# rbbb.net
KiCad netlist of a schematic drawn in EAGLE
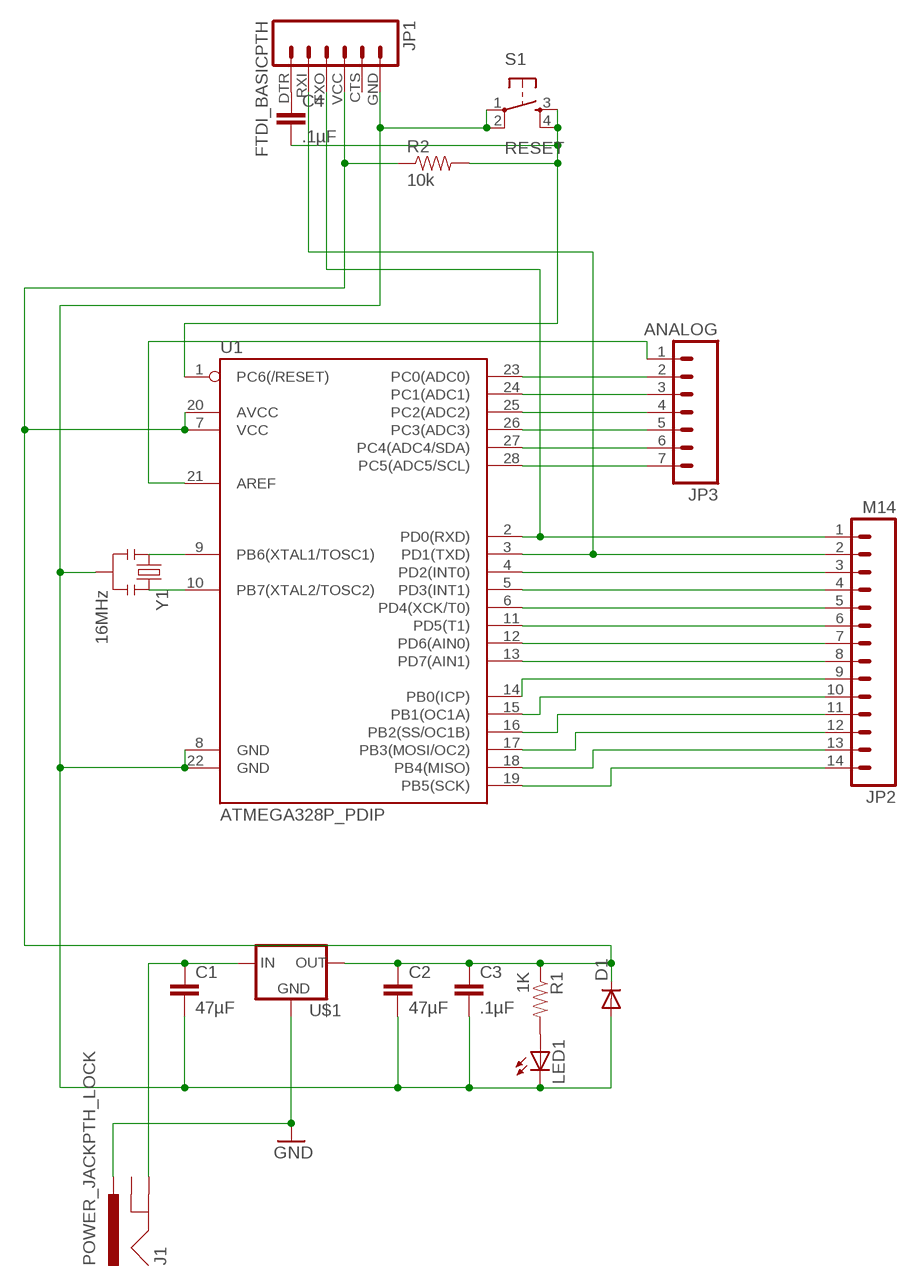
[diagram p0: schematic, sheet 1]

(export (version "E")
  (design (tool "Eeschema 10.0.6"))
  (components
    (comp (ref "C1")
      (value "47µF")
      (footprint "eagle-import:CAP-PTH-SMALL")
      (libsource (lib "eagle-import") (part "CAPPTH"))
    )
    (comp (ref "C2")
      (value "47µF")
      (footprint "eagle-import:CAP-PTH-SMALL")
      (libsource (lib "eagle-import") (part "CAPPTH"))
    )
    (comp (ref "C3")
      (value ".1µF")
      (footprint "eagle-import:CAP-PTH-SMALL")
      (libsource (lib "eagle-import") (part "CAPPTH"))
    )
    (comp (ref "C4")
      (value ".1µF")
      (footprint "eagle-import:CAP-PTH-SMALL")
      (libsource (lib "eagle-import") (part "CAPPTH"))
    )
    (comp (ref "D1")
      (value "DIODEPTH")
      (footprint "eagle-import:DIODE-1N4001")
      (libsource (lib "eagle-import") (part "DIODEPTH"))
    )
    (comp (ref "J1")
      (value "POWER_JACKPTH_LOCK")
      (footprint "eagle-import:POWER_JACK_PTH_LOCK")
      (libsource (lib "eagle-import") (part "POWER_JACKPTH_LOCK"))
    )
    (comp (ref "JP1")
      (value "FTDI_BASICPTH")
      (footprint "eagle-import:FTDI_BASIC")
      (libsource (lib "eagle-import") (part "FTDI_BASICPTH"))
    )
    (comp (ref "JP2")
      (value "M14")
      (footprint "eagle-import:1X14")
      (libsource (lib "eagle-import") (part "M14"))
    )
    (comp (ref "JP3")
      (value "ANALOG")
      (footprint "eagle-import:1X07")
      (libsource (lib "eagle-import") (part "M07"))
    )
    (comp (ref "LED1")
      (value "LED5MM")
      (footprint "eagle-import:LED5MM")
      (libsource (lib "eagle-import") (part "LED5MM"))
    )
    (comp (ref "R1")
      (value "1K")
      (footprint "eagle-import:AXIAL-0.4")
      (libsource (lib "eagle-import") (part "RESISTORPTH-1/4W"))
    )
    (comp (ref "R2")
      (value "10k")
      (footprint "eagle-import:AXIAL-0.4")
      (libsource (lib "eagle-import") (part "RESISTORPTH-1/4W"))
    )
    (comp (ref "S1")
      (value "RESET")
      (footprint "eagle-import:TACTILE-PTH")
      (libsource (lib "eagle-import") (part "TAC_SWITCHPTH"))
    )
    (comp (ref "U$1")
      (value "V_REG_78XX-TO-220")
      (footprint "eagle-import:TO-220-ALT")
      (libsource (lib "eagle-import") (part "V_REG_78XX-TO-220"))
    )
    (comp (ref "U1")
      (value "ATMEGA328P_PDIP")
      (footprint "eagle-import:DIL28-3")
      (libsource (lib "eagle-import") (part "ATMEGA328P_PDIP"))
    )
    (comp (ref "Y1")
      (value "16MHz")
      (footprint "eagle-import:RESONATOR-PTH")
      (libsource (lib "eagle-import") (part "RESONATORPTH"))
    )
  )
  (nets
    (net (code "1") (name "GND") (class "Default")
      (node (ref "J1") (pin "PWR") (pinfunction "PWR_PWR") (pintype "bidirectional"))
      (node (ref "U$1") (pin "GND") (pinfunction "GND_GND") (pintype "input"))
    )
    (net (code "2") (name "Net-(C1-Pad1)") (class "Default")
      (node (ref "C1") (pin "1") (pinfunction "1_1") (pintype "passive"))
      (node (ref "J1") (pin "GND") (pinfunction "GND_GND") (pintype "bidirectional"))
      (node (ref "U$1") (pin "IN") (pinfunction "IN_IN") (pintype "input"))
    )
    (net (code "3") (name "Net-(JP1-1)") (class "Default")
      (node (ref "C4") (pin "1") (pinfunction "1_1") (pintype "passive"))
      (node (ref "JP1") (pin "DTR") (pinfunction "1_DTR") (pintype "passive"))
    )
    (net (code "4") (name "Net-(JP1-2)") (class "Default")
      (node (ref "JP1") (pin "RXI") (pinfunction "2_RXI") (pintype "passive"))
      (node (ref "JP2") (pin "2") (pinfunction "2_2") (pintype "passive"))
      (node (ref "U1") (pin "3") (pinfunction "PD1(TXD)_3") (pintype "bidirectional"))
    )
    (net (code "5") (name "Net-(JP1-3)") (class "Default")
      (node (ref "JP1") (pin "TXO") (pinfunction "3_TXO") (pintype "passive"))
      (node (ref "JP2") (pin "1") (pinfunction "1_1") (pintype "passive"))
      (node (ref "U1") (pin "2") (pinfunction "PD0(RXD)_2") (pintype "bidirectional"))
    )
    (net (code "6") (name "Net-(JP1-4)") (class "Default")
      (node (ref "C2") (pin "1") (pinfunction "1_1") (pintype "passive"))
      (node (ref "C3") (pin "1") (pinfunction "1_1") (pintype "passive"))
      (node (ref "D1") (pin "C") (pinfunction "C_C") (pintype "passive"))
      (node (ref "JP1") (pin "VCC") (pinfunction "4_VCC") (pintype "passive"))
      (node (ref "R1") (pin "P$1") (pinfunction "1_P$1") (pintype "passive"))
      (node (ref "R2") (pin "P$1") (pinfunction "1_P$1") (pintype "passive"))
      (node (ref "U$1") (pin "OUT") (pinfunction "OUT_OUT") (pintype "output"))
      (node (ref "U1") (pin "20") (pinfunction "AVCC_20") (pintype "bidirectional"))
      (node (ref "U1") (pin "7") (pinfunction "VCC_7") (pintype "bidirectional"))
    )
    (net (code "7") (name "Net-(JP1-6)") (class "Default")
      (node (ref "C1") (pin "2") (pinfunction "2_2") (pintype "passive"))
      (node (ref "C2") (pin "2") (pinfunction "2_2") (pintype "passive"))
      (node (ref "C3") (pin "2") (pinfunction "2_2") (pintype "passive"))
      (node (ref "D1") (pin "A") (pinfunction "A_A") (pintype "passive"))
      (node (ref "JP1") (pin "GND") (pinfunction "6_GND") (pintype "passive"))
      (node (ref "LED1") (pin "K") (pinfunction "C_K") (pintype "passive"))
      (node (ref "S1") (pin "1") (pinfunction "1_1") (pintype "passive"))
      (node (ref "S1") (pin "2") (pinfunction "2_2") (pintype "passive"))
      (node (ref "U1") (pin "22") (pinfunction "GND_22") (pintype "bidirectional"))
      (node (ref "U1") (pin "8") (pinfunction "GND_8") (pintype "bidirectional"))
      (node (ref "Y1") (pin "2") (pinfunction "2_2") (pintype "passive"))
    )
    (net (code "8") (name "Net-(R1-2)") (class "Default")
      (node (ref "LED1") (pin "A") (pinfunction "A_A") (pintype "passive"))
      (node (ref "R1") (pin "P$2") (pinfunction "2_P$2") (pintype "passive"))
    )
    (net (code "9") (name "Net-(R2-2)") (class "Default")
      (node (ref "C4") (pin "2") (pinfunction "2_2") (pintype "passive"))
      (node (ref "R2") (pin "P$2") (pinfunction "2_P$2") (pintype "passive"))
      (node (ref "S1") (pin "3") (pinfunction "3_3") (pintype "passive"))
      (node (ref "S1") (pin "4") (pinfunction "4_4") (pintype "passive"))
      (node (ref "U1") (pin "1") (pinfunction "PC6(/RESET)_1") (pintype "bidirectional"))
    )
    (net (code "10") (name "Net-(U1-AREF)") (class "Default")
      (node (ref "JP3") (pin "1") (pinfunction "1_1") (pintype "passive"))
      (node (ref "U1") (pin "21") (pinfunction "AREF_21") (pintype "bidirectional"))
    )
    (net (code "11") (name "Net-(U1-PB0(ICP))") (class "Default")
      (node (ref "JP2") (pin "9") (pinfunction "9_9") (pintype "passive"))
      (node (ref "U1") (pin "14") (pinfunction "PB0(ICP)_14") (pintype "bidirectional"))
    )
    (net (code "12") (name "Net-(U1-PB1(OC1A))") (class "Default")
      (node (ref "JP2") (pin "10") (pinfunction "10_10") (pintype "passive"))
      (node (ref "U1") (pin "15") (pinfunction "PB1(OC1A)_15") (pintype "bidirectional"))
    )
    (net (code "13") (name "Net-(U1-PB2(SS{slash}OC1B))") (class "Default")
      (node (ref "JP2") (pin "11") (pinfunction "11_11") (pintype "passive"))
      (node (ref "U1") (pin "16") (pinfunction "PB2(SS/OC1B)_16") (pintype "bidirectional"))
    )
    (net (code "14") (name "Net-(U1-PB3(MOSI{slash}OC2))") (class "Default")
      (node (ref "JP2") (pin "12") (pinfunction "12_12") (pintype "passive"))
      (node (ref "U1") (pin "17") (pinfunction "PB3(MOSI/OC2)_17") (pintype "bidirectional"))
    )
    (net (code "15") (name "Net-(U1-PB4(MISO))") (class "Default")
      (node (ref "JP2") (pin "13") (pinfunction "13_13") (pintype "passive"))
      (node (ref "U1") (pin "18") (pinfunction "PB4(MISO)_18") (pintype "bidirectional"))
    )
    (net (code "16") (name "Net-(U1-PB5(SCK))") (class "Default")
      (node (ref "JP2") (pin "14") (pinfunction "14_14") (pintype "passive"))
      (node (ref "U1") (pin "19") (pinfunction "PB5(SCK)_19") (pintype "bidirectional"))
    )
    (net (code "17") (name "Net-(U1-PB6(XTAL1{slash}TOSC1))") (class "Default")
      (node (ref "U1") (pin "9") (pinfunction "PB6(XTAL1/TOSC1)_9") (pintype "bidirectional"))
      (node (ref "Y1") (pin "1") (pinfunction "1_1") (pintype "passive"))
    )
    (net (code "18") (name "Net-(U1-PB7(XTAL2{slash}TOSC2))") (class "Default")
      (node (ref "U1") (pin "10") (pinfunction "PB7(XTAL2/TOSC2)_10") (pintype "bidirectional"))
      (node (ref "Y1") (pin "3") (pinfunction "3_3") (pintype "passive"))
    )
    (net (code "19") (name "Net-(U1-PC0(ADC0))") (class "Default")
      (node (ref "JP3") (pin "2") (pinfunction "2_2") (pintype "passive"))
      (node (ref "U1") (pin "23") (pinfunction "PC0(ADC0)_23") (pintype "bidirectional"))
    )
    (net (code "20") (name "Net-(U1-PC1(ADC1))") (class "Default")
      (node (ref "JP3") (pin "3") (pinfunction "3_3") (pintype "passive"))
      (node (ref "U1") (pin "24") (pinfunction "PC1(ADC1)_24") (pintype "bidirectional"))
    )
    (net (code "21") (name "Net-(U1-PC2(ADC2))") (class "Default")
      (node (ref "JP3") (pin "4") (pinfunction "4_4") (pintype "passive"))
      (node (ref "U1") (pin "25") (pinfunction "PC2(ADC2)_25") (pintype "bidirectional"))
    )
    (net (code "22") (name "Net-(U1-PC3(ADC3))") (class "Default")
      (node (ref "JP3") (pin "5") (pinfunction "5_5") (pintype "passive"))
      (node (ref "U1") (pin "26") (pinfunction "PC3(ADC3)_26") (pintype "bidirectional"))
    )
    (net (code "23") (name "Net-(U1-PC4(ADC4{slash}SDA))") (class "Default")
      (node (ref "JP3") (pin "6") (pinfunction "6_6") (pintype "passive"))
      (node (ref "U1") (pin "27") (pinfunction "PC4(ADC4/SDA)_27") (pintype "bidirectional"))
    )
    (net (code "24") (name "Net-(U1-PC5(ADC5{slash}SCL))") (class "Default")
      (node (ref "JP3") (pin "7") (pinfunction "7_7") (pintype "passive"))
      (node (ref "U1") (pin "28") (pinfunction "PC5(ADC5/SCL)_28") (pintype "bidirectional"))
    )
    (net (code "25") (name "Net-(U1-PD2(INT0))") (class "Default")
      (node (ref "JP2") (pin "3") (pinfunction "3_3") (pintype "passive"))
      (node (ref "U1") (pin "4") (pinfunction "PD2(INT0)_4") (pintype "bidirectional"))
    )
    (net (code "26") (name "Net-(U1-PD3(INT1))") (class "Default")
      (node (ref "JP2") (pin "4") (pinfunction "4_4") (pintype "passive"))
      (node (ref "U1") (pin "5") (pinfunction "PD3(INT1)_5") (pintype "bidirectional"))
    )
    (net (code "27") (name "Net-(U1-PD4(XCK{slash}T0))") (class "Default")
      (node (ref "JP2") (pin "5") (pinfunction "5_5") (pintype "passive"))
      (node (ref "U1") (pin "6") (pinfunction "PD4(XCK/T0)_6") (pintype "bidirectional"))
    )
    (net (code "28") (name "Net-(U1-PD5(T1))") (class "Default")
      (node (ref "JP2") (pin "6") (pinfunction "6_6") (pintype "passive"))
      (node (ref "U1") (pin "11") (pinfunction "PD5(T1)_11") (pintype "bidirectional"))
    )
    (net (code "29") (name "Net-(U1-PD6(AIN0))") (class "Default")
      (node (ref "JP2") (pin "7") (pinfunction "7_7") (pintype "passive"))
      (node (ref "U1") (pin "12") (pinfunction "PD6(AIN0)_12") (pintype "bidirectional"))
    )
    (net (code "30") (name "Net-(U1-PD7(AIN1))") (class "Default")
      (node (ref "JP2") (pin "8") (pinfunction "8_8") (pintype "passive"))
      (node (ref "U1") (pin "13") (pinfunction "PD7(AIN1)_13") (pintype "bidirectional"))
    )
    (net (code "31") (name "unconnected-(J1-PadGNDBREAK)") (class "Default")
      (node (ref "J1") (pin "GNDBREAK") (pinfunction "GNDBREAK_GNDBREAK") (pintype "bidirectional"))
    )
    (net (code "32") (name "unconnected-(JP1-5-PadCTS)") (class "Default")
      (node (ref "JP1") (pin "CTS") (pinfunction "5_CTS") (pintype "passive"))
    )
  )
)
